# BreakBoard.net
KiCad netlist of a schematic drawn in Altium Designer
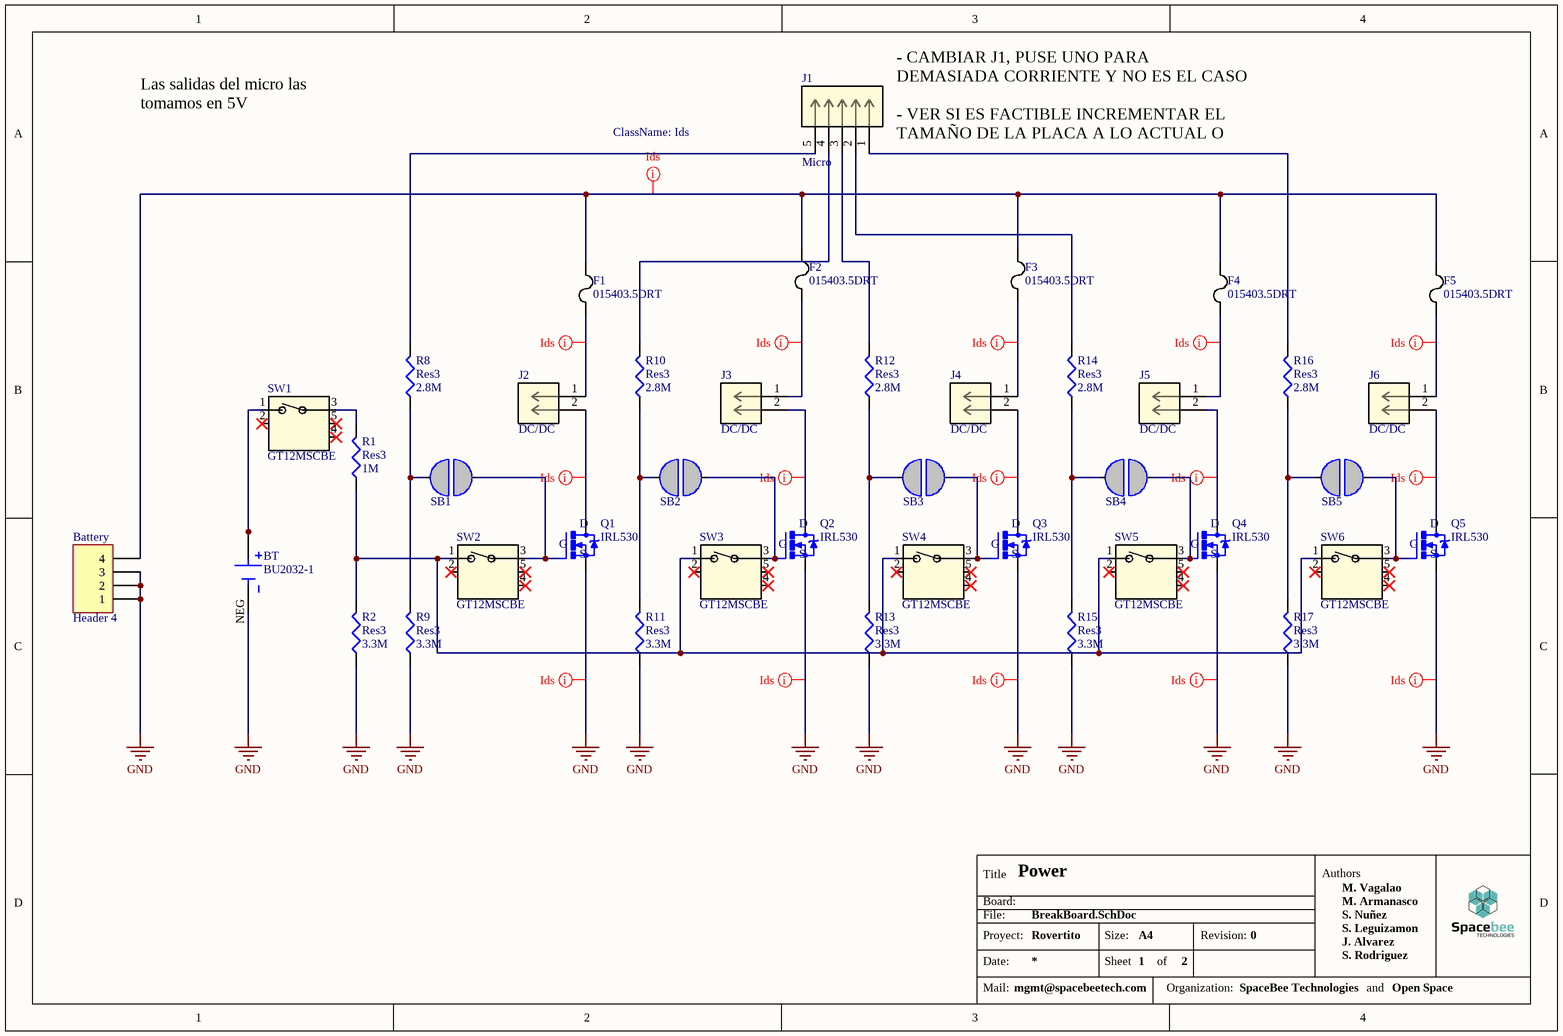
[diagram p0: BreakBoard.SchDoc]

(export (version "E")
  (design (tool "Eeschema 10.0.6"))
  (components
    (comp (ref "Battery")
      (value "Header 4")
      (footprint "292132-4:292132-4_TYC")
      (description "Header, 4-Pin")
      (fields (field (name "PUBLISHER") "Altium Limited"))
      (libsource (lib "Miscellaneous Connectors") (part "Header 4"))
    )
    (comp (ref "BT")
      (value "BU2032-1")
      (footprint "BAT_BU2032-1:BAT_BU2032-1")
      (description "HOLDER CR2032 W/ PC PINS")
      (fields (field (name "MF") "MPD"))
      (libsource (lib "BU2032-1") (part "BU2032-1"))
    )
    (comp (ref "F1")
      (value "015403.5DRT")
      (footprint "FUSE_Bourns")
      (description "No Description Available")
      (fields (field (name "COPYRIGHT") "Copyright (C) 2022 Ultra Librarian. All rights reserved."))
      (libsource (lib "015403P5DRT") (part "015403.5DRT"))
    )
    (comp (ref "F2")
      (value "015403.5DRT")
      (footprint "FUSE_Bourns")
      (description "No Description Available")
      (fields (field (name "COPYRIGHT") "Copyright (C) 2022 Ultra Librarian. All rights reserved."))
      (libsource (lib "015403P5DRT") (part "015403.5DRT"))
    )
    (comp (ref "F3")
      (value "015403.5DRT")
      (footprint "FUSE_Bourns")
      (description "No Description Available")
      (fields (field (name "COPYRIGHT") "Copyright (C) 2022 Ultra Librarian. All rights reserved."))
      (libsource (lib "015403P5DRT") (part "015403.5DRT"))
    )
    (comp (ref "F4")
      (value "015403.5DRT")
      (footprint "FUSE_Bourns")
      (description "No Description Available")
      (fields (field (name "COPYRIGHT") "Copyright (C) 2022 Ultra Librarian. All rights reserved."))
      (libsource (lib "015403P5DRT") (part "015403.5DRT"))
    )
    (comp (ref "F5")
      (value "015403.5DRT")
      (footprint "FUSE_Bourns")
      (description "No Description Available")
      (fields (field (name "COPYRIGHT") "Copyright (C) 2022 Ultra Librarian. All rights reserved."))
      (libsource (lib "015403P5DRT") (part "015403.5DRT"))
    )
    (comp (ref "J1")
      (value "Micro")
      (footprint "MOLEX_532610571")
      (description "No Description Available")
      (fields
        (field (name "MANUFACTURER_PART_NUMBER") "HTSW-105-07-L-S")
        (field (name "COPYRIGHT") "Copyright (C) 2022 Ultra Librarian. All rights reserved.")
      )
      (libsource (lib "HTSW-105-07-L-S") (part "HTSW-105-07-L-S"))
    )
    (comp (ref "J2")
      (value "DC/DC")
      (footprint "CON_1054302102_MOL")
      (description "No Description Available")
      (fields
        (field (name "MANUFACTURER_PART_NUMBER") "TSW-102-05-T-S")
        (field (name "COPYRIGHT") "Copyright (C) 2022 Ultra Librarian. All rights reserved.")
      )
      (libsource (lib "TSW-102-05-T-S") (part "TSW-102-05-T-S"))
    )
    (comp (ref "J3")
      (value "DC/DC")
      (footprint "CON_1054302102_MOL")
      (description "No Description Available")
      (fields
        (field (name "MANUFACTURER_PART_NUMBER") "TSW-102-05-T-S")
        (field (name "COPYRIGHT") "Copyright (C) 2022 Ultra Librarian. All rights reserved.")
      )
      (libsource (lib "TSW-102-05-T-S") (part "TSW-102-05-T-S"))
    )
    (comp (ref "J4")
      (value "DC/DC")
      (footprint "CON_1054302102_MOL")
      (description "No Description Available")
      (fields
        (field (name "MANUFACTURER_PART_NUMBER") "TSW-102-05-T-S")
        (field (name "COPYRIGHT") "Copyright (C) 2022 Ultra Librarian. All rights reserved.")
      )
      (libsource (lib "TSW-102-05-T-S") (part "TSW-102-05-T-S"))
    )
    (comp (ref "J5")
      (value "DC/DC")
      (footprint "CON_1054302102_MOL")
      (description "No Description Available")
      (fields
        (field (name "MANUFACTURER_PART_NUMBER") "TSW-102-05-T-S")
        (field (name "COPYRIGHT") "Copyright (C) 2022 Ultra Librarian. All rights reserved.")
      )
      (libsource (lib "TSW-102-05-T-S") (part "TSW-102-05-T-S"))
    )
    (comp (ref "J6")
      (value "DC/DC")
      (footprint "CON_1054302102_MOL")
      (description "No Description Available")
      (fields
        (field (name "MANUFACTURER_PART_NUMBER") "TSW-102-05-T-S")
        (field (name "COPYRIGHT") "Copyright (C) 2022 Ultra Librarian. All rights reserved.")
      )
      (libsource (lib "TSW-102-05-T-S") (part "TSW-102-05-T-S"))
    )
    (comp (ref "Q1")
      (value "IRL530")
      (footprint "IRL530NSTRLPBF:IRL530NSTRLPBF_INF")
      (description "N-Channel 100V 15A (Tc) 88W (Tc) Through Hole TO-220AB")
      (fields (field (name "MF") "Vishay / Siliconix"))
      (libsource (lib "IRL530") (part "IRL530"))
    )
    (comp (ref "Q2")
      (value "IRL530")
      (footprint "IRL530NSTRLPBF:IRL530NSTRLPBF_INF")
      (description "N-Channel 100V 15A (Tc) 88W (Tc) Through Hole TO-220AB")
      (fields (field (name "MF") "Vishay / Siliconix"))
      (libsource (lib "IRL530") (part "IRL530"))
    )
    (comp (ref "Q3")
      (value "IRL530")
      (footprint "IRL530NSTRLPBF:IRL530NSTRLPBF_INF")
      (description "N-Channel 100V 15A (Tc) 88W (Tc) Through Hole TO-220AB")
      (fields (field (name "MF") "Vishay / Siliconix"))
      (libsource (lib "IRL530") (part "IRL530"))
    )
    (comp (ref "Q4")
      (value "IRL530")
      (footprint "IRL530NSTRLPBF:IRL530NSTRLPBF_INF")
      (description "N-Channel 100V 15A (Tc) 88W (Tc) Through Hole TO-220AB")
      (fields (field (name "MF") "Vishay / Siliconix"))
      (libsource (lib "IRL530") (part "IRL530"))
    )
    (comp (ref "Q5")
      (value "IRL530")
      (footprint "IRL530NSTRLPBF:IRL530NSTRLPBF_INF")
      (description "N-Channel 100V 15A (Tc) 88W (Tc) Through Hole TO-220AB")
      (fields (field (name "MF") "Vishay / Siliconix"))
      (libsource (lib "IRL530") (part "IRL530"))
    )
    (comp (ref "R1")
      (value "Res3")
      (footprint "J1-0603")
      (description "Resistor")
      (fields (field (name "ALTIUM_VALUE") "1M") (field (name "PUBLISHER") "Altium Limited"))
      (libsource (lib "Miscellaneous Devices") (part "Res3"))
    )
    (comp (ref "R2")
      (value "Res3")
      (footprint "J1-0603")
      (description "Resistor")
      (fields (field (name "ALTIUM_VALUE") "3.3M") (field (name "PUBLISHER") "Altium Limited"))
      (libsource (lib "Miscellaneous Devices") (part "Res3"))
    )
    (comp (ref "R8")
      (value "Res3")
      (footprint "RESC2012X60N:RESC2012X60N")
      (description "Resistor")
      (fields (field (name "ALTIUM_VALUE") "2.8M") (field (name "PUBLISHER") "Altium Limited"))
      (libsource (lib "Miscellaneous Devices") (part "Res3"))
    )
    (comp (ref "R9")
      (value "Res3")
      (footprint "J1-0603")
      (description "Resistor")
      (fields (field (name "ALTIUM_VALUE") "3.3M") (field (name "PUBLISHER") "Altium Limited"))
      (libsource (lib "Miscellaneous Devices") (part "Res3"))
    )
    (comp (ref "R10")
      (value "Res3")
      (footprint "RESC2012X60N:RESC2012X60N")
      (description "Resistor")
      (fields (field (name "ALTIUM_VALUE") "2.8M") (field (name "PUBLISHER") "Altium Limited"))
      (libsource (lib "Miscellaneous Devices") (part "Res3"))
    )
    (comp (ref "R11")
      (value "Res3")
      (footprint "J1-0603")
      (description "Resistor")
      (fields (field (name "ALTIUM_VALUE") "3.3M") (field (name "PUBLISHER") "Altium Limited"))
      (libsource (lib "Miscellaneous Devices") (part "Res3"))
    )
    (comp (ref "R12")
      (value "Res3")
      (footprint "RESC2012X60N:RESC2012X60N")
      (description "Resistor")
      (fields (field (name "ALTIUM_VALUE") "2.8M") (field (name "PUBLISHER") "Altium Limited"))
      (libsource (lib "Miscellaneous Devices") (part "Res3"))
    )
    (comp (ref "R13")
      (value "Res3")
      (footprint "J1-0603")
      (description "Resistor")
      (fields (field (name "ALTIUM_VALUE") "3.3M") (field (name "PUBLISHER") "Altium Limited"))
      (libsource (lib "Miscellaneous Devices") (part "Res3"))
    )
    (comp (ref "R14")
      (value "Res3")
      (footprint "RESC2012X60N:RESC2012X60N")
      (description "Resistor")
      (fields (field (name "ALTIUM_VALUE") "2.8M") (field (name "PUBLISHER") "Altium Limited"))
      (libsource (lib "Miscellaneous Devices") (part "Res3"))
    )
    (comp (ref "R15")
      (value "Res3")
      (footprint "J1-0603")
      (description "Resistor")
      (fields (field (name "ALTIUM_VALUE") "3.3M") (field (name "PUBLISHER") "Altium Limited"))
      (libsource (lib "Miscellaneous Devices") (part "Res3"))
    )
    (comp (ref "R16")
      (value "Res3")
      (footprint "RESC2012X60N:RESC2012X60N")
      (description "Resistor")
      (fields (field (name "ALTIUM_VALUE") "2.8M") (field (name "PUBLISHER") "Altium Limited"))
      (libsource (lib "Miscellaneous Devices") (part "Res3"))
    )
    (comp (ref "R17")
      (value "Res3")
      (footprint "J1-0603")
      (description "Resistor")
      (fields (field (name "ALTIUM_VALUE") "3.3M") (field (name "PUBLISHER") "Altium Limited"))
      (libsource (lib "Miscellaneous Devices") (part "Res3"))
    )
    (comp (ref "SB1")
      (value "SolderBridge")
      (footprint "PCBComponent_1")
      (libsource (lib "SolderBridge") (part "Component_1"))
    )
    (comp (ref "SB2")
      (value "SolderBridge")
      (footprint "PCBComponent_1")
      (libsource (lib "SolderBridge") (part "Component_1"))
    )
    (comp (ref "SB3")
      (value "SolderBridge")
      (footprint "PCBComponent_1")
      (libsource (lib "SolderBridge") (part "Component_1"))
    )
    (comp (ref "SB4")
      (value "SolderBridge")
      (footprint "PCBComponent_1")
      (libsource (lib "SolderBridge") (part "Component_1"))
    )
    (comp (ref "SB5")
      (value "SolderBridge")
      (footprint "PCBComponent_1")
      (libsource (lib "SolderBridge") (part "Component_1"))
    )
    (comp (ref "SW1")
      (value "GT12MSCBE")
      (footprint "SW5_GT12MSCBE_CNK")
      (description "No Description Available")
      (fields (field (name "COPYRIGHT") "Copyright (C) 2022 Ultra Librarian. All rights reserved."))
      (libsource (lib "GT12MSCBE") (part "GT12MSCBE"))
    )
    (comp (ref "SW2")
      (value "GT12MSCBE")
      (footprint "SW5_GT12MSCBE_CNK")
      (description "No Description Available")
      (fields (field (name "COPYRIGHT") "Copyright (C) 2022 Ultra Librarian. All rights reserved."))
      (libsource (lib "GT12MSCBE") (part "GT12MSCBE"))
    )
    (comp (ref "SW3")
      (value "GT12MSCBE")
      (footprint "SW5_GT12MSCBE_CNK")
      (description "No Description Available")
      (fields (field (name "COPYRIGHT") "Copyright (C) 2022 Ultra Librarian. All rights reserved."))
      (libsource (lib "GT12MSCBE") (part "GT12MSCBE"))
    )
    (comp (ref "SW4")
      (value "GT12MSCBE")
      (footprint "SW5_GT12MSCBE_CNK")
      (description "No Description Available")
      (fields (field (name "COPYRIGHT") "Copyright (C) 2022 Ultra Librarian. All rights reserved."))
      (libsource (lib "GT12MSCBE") (part "GT12MSCBE"))
    )
    (comp (ref "SW5")
      (value "GT12MSCBE")
      (footprint "SW5_GT12MSCBE_CNK")
      (description "No Description Available")
      (fields (field (name "COPYRIGHT") "Copyright (C) 2022 Ultra Librarian. All rights reserved."))
      (libsource (lib "GT12MSCBE") (part "GT12MSCBE"))
    )
    (comp (ref "SW6")
      (value "GT12MSCBE")
      (footprint "SW5_GT12MSCBE_CNK")
      (description "No Description Available")
      (fields (field (name "COPYRIGHT") "Copyright (C) 2022 Ultra Librarian. All rights reserved."))
      (libsource (lib "GT12MSCBE") (part "GT12MSCBE"))
    )
  )
  (nets
    (net (code "1") (name "GND") (class "Default")
      (node (ref "BT") (pin "NEG") (pinfunction "NEG_NEG") (pintype "passive"))
      (node (ref "Battery") (pin "1") (pinfunction "1_1") (pintype "passive"))
      (node (ref "Battery") (pin "2") (pinfunction "2_2") (pintype "passive"))
      (node (ref "Battery") (pin "3") (pinfunction "3_3") (pintype "passive"))
      (node (ref "Q1") (pin "3") (pinfunction "S_3") (pintype "passive"))
      (node (ref "Q2") (pin "3") (pinfunction "S_3") (pintype "passive"))
      (node (ref "Q3") (pin "3") (pinfunction "S_3") (pintype "passive"))
      (node (ref "Q4") (pin "3") (pinfunction "S_3") (pintype "passive"))
      (node (ref "Q5") (pin "3") (pinfunction "S_3") (pintype "passive"))
      (node (ref "R11") (pin "1") (pinfunction "1_1") (pintype "passive"))
      (node (ref "R13") (pin "1") (pinfunction "1_1") (pintype "passive"))
      (node (ref "R15") (pin "1") (pinfunction "1_1") (pintype "passive"))
      (node (ref "R17") (pin "1") (pinfunction "1_1") (pintype "passive"))
      (node (ref "R2") (pin "1") (pinfunction "1_1") (pintype "passive"))
      (node (ref "R9") (pin "1") (pinfunction "1_1") (pintype "passive"))
    )
    (net (code "2") (name "Net-(BT-POS-PadS1+)") (class "Default")
      (node (ref "BT") (pin "S1+") (pinfunction "POS_S1+") (pintype "passive"))
      (node (ref "BT") (pin "S2+") (pinfunction "POS_S2+") (pintype "passive"))
      (node (ref "SW1") (pin "1") (pinfunction "1_1") (pintype "passive"))
    )
    (net (code "3") (name "Net-(Battery-Pad4)") (class "Default")
      (node (ref "Battery") (pin "4") (pinfunction "4_4") (pintype "passive"))
      (node (ref "F1") (pin "2") (pinfunction "2_2") (pintype "passive"))
      (node (ref "F2") (pin "2") (pinfunction "2_2") (pintype "passive"))
      (node (ref "F3") (pin "2") (pinfunction "2_2") (pintype "passive"))
      (node (ref "F4") (pin "2") (pinfunction "2_2") (pintype "passive"))
      (node (ref "F5") (pin "2") (pinfunction "2_2") (pintype "passive"))
    )
    (net (code "4") (name "Net-(F1-Pad1)") (class "Default")
      (node (ref "F1") (pin "1") (pinfunction "1_1") (pintype "passive"))
      (node (ref "J2") (pin "1") (pinfunction "1_1") (pintype "passive"))
    )
    (net (code "5") (name "Net-(F2-Pad1)") (class "Default")
      (node (ref "F2") (pin "1") (pinfunction "1_1") (pintype "passive"))
      (node (ref "J3") (pin "1") (pinfunction "1_1") (pintype "passive"))
    )
    (net (code "6") (name "Net-(F3-Pad1)") (class "Default")
      (node (ref "F3") (pin "1") (pinfunction "1_1") (pintype "passive"))
      (node (ref "J4") (pin "1") (pinfunction "1_1") (pintype "passive"))
    )
    (net (code "7") (name "Net-(F4-Pad1)") (class "Default")
      (node (ref "F4") (pin "1") (pinfunction "1_1") (pintype "passive"))
      (node (ref "J5") (pin "1") (pinfunction "1_1") (pintype "passive"))
    )
    (net (code "8") (name "Net-(F5-Pad1)") (class "Default")
      (node (ref "F5") (pin "1") (pinfunction "1_1") (pintype "passive"))
      (node (ref "J6") (pin "1") (pinfunction "1_1") (pintype "passive"))
    )
    (net (code "9") (name "Net-(J1-Pad1)") (class "Default")
      (node (ref "J1") (pin "1") (pinfunction "1_1") (pintype "passive"))
      (node (ref "R16") (pin "2") (pinfunction "2_2") (pintype "passive"))
    )
    (net (code "10") (name "Net-(J1-Pad2)") (class "Default")
      (node (ref "J1") (pin "2") (pinfunction "2_2") (pintype "passive"))
      (node (ref "R14") (pin "2") (pinfunction "2_2") (pintype "passive"))
    )
    (net (code "11") (name "Net-(J1-Pad3)") (class "Default")
      (node (ref "J1") (pin "3") (pinfunction "3_3") (pintype "passive"))
      (node (ref "R12") (pin "2") (pinfunction "2_2") (pintype "passive"))
    )
    (net (code "12") (name "Net-(J1-Pad4)") (class "Default")
      (node (ref "J1") (pin "4") (pinfunction "4_4") (pintype "passive"))
      (node (ref "R10") (pin "2") (pinfunction "2_2") (pintype "passive"))
    )
    (net (code "13") (name "Net-(J1-Pad5)") (class "Default")
      (node (ref "J1") (pin "5") (pinfunction "5_5") (pintype "passive"))
      (node (ref "R8") (pin "2") (pinfunction "2_2") (pintype "passive"))
    )
    (net (code "14") (name "Net-(Q1-D)") (class "Default")
      (node (ref "J2") (pin "2") (pinfunction "2_2") (pintype "passive"))
      (node (ref "Q1") (pin "2") (pinfunction "D_2") (pintype "passive"))
    )
    (net (code "15") (name "Net-(Q1-G)") (class "Default")
      (node (ref "Q1") (pin "1") (pinfunction "G_1") (pintype "passive"))
      (node (ref "SB1") (pin "0") (pinfunction "0_0") (pintype "passive"))
      (node (ref "SW2") (pin "3") (pinfunction "3_3") (pintype "passive"))
    )
    (net (code "16") (name "Net-(Q2-D)") (class "Default")
      (node (ref "J3") (pin "2") (pinfunction "2_2") (pintype "passive"))
      (node (ref "Q2") (pin "2") (pinfunction "D_2") (pintype "passive"))
    )
    (net (code "17") (name "Net-(Q2-G)") (class "Default")
      (node (ref "Q2") (pin "1") (pinfunction "G_1") (pintype "passive"))
      (node (ref "SB2") (pin "0") (pinfunction "0_0") (pintype "passive"))
      (node (ref "SW3") (pin "3") (pinfunction "3_3") (pintype "passive"))
    )
    (net (code "18") (name "Net-(Q3-D)") (class "Default")
      (node (ref "J4") (pin "2") (pinfunction "2_2") (pintype "passive"))
      (node (ref "Q3") (pin "2") (pinfunction "D_2") (pintype "passive"))
    )
    (net (code "19") (name "Net-(Q3-G)") (class "Default")
      (node (ref "Q3") (pin "1") (pinfunction "G_1") (pintype "passive"))
      (node (ref "SB3") (pin "0") (pinfunction "0_0") (pintype "passive"))
      (node (ref "SW4") (pin "3") (pinfunction "3_3") (pintype "passive"))
    )
    (net (code "20") (name "Net-(Q4-D)") (class "Default")
      (node (ref "J5") (pin "2") (pinfunction "2_2") (pintype "passive"))
      (node (ref "Q4") (pin "2") (pinfunction "D_2") (pintype "passive"))
    )
    (net (code "21") (name "Net-(Q4-G)") (class "Default")
      (node (ref "Q4") (pin "1") (pinfunction "G_1") (pintype "passive"))
      (node (ref "SB4") (pin "0") (pinfunction "0_0") (pintype "passive"))
      (node (ref "SW5") (pin "3") (pinfunction "3_3") (pintype "passive"))
    )
    (net (code "22") (name "Net-(Q5-D)") (class "Default")
      (node (ref "J6") (pin "2") (pinfunction "2_2") (pintype "passive"))
      (node (ref "Q5") (pin "2") (pinfunction "D_2") (pintype "passive"))
    )
    (net (code "23") (name "Net-(Q5-G)") (class "Default")
      (node (ref "Q5") (pin "1") (pinfunction "G_1") (pintype "passive"))
      (node (ref "SB5") (pin "0") (pinfunction "0_0") (pintype "passive"))
      (node (ref "SW6") (pin "3") (pinfunction "3_3") (pintype "passive"))
    )
    (net (code "24") (name "Net-(R1-Pad1)") (class "Default")
      (node (ref "R1") (pin "1") (pinfunction "1_1") (pintype "passive"))
      (node (ref "R2") (pin "2") (pinfunction "2_2") (pintype "passive"))
      (node (ref "SW2") (pin "1") (pinfunction "1_1") (pintype "passive"))
      (node (ref "SW3") (pin "1") (pinfunction "1_1") (pintype "passive"))
      (node (ref "SW4") (pin "1") (pinfunction "1_1") (pintype "passive"))
      (node (ref "SW5") (pin "1") (pinfunction "1_1") (pintype "passive"))
      (node (ref "SW6") (pin "1") (pinfunction "1_1") (pintype "passive"))
    )
    (net (code "25") (name "Net-(R1-Pad2)") (class "Default")
      (node (ref "R1") (pin "2") (pinfunction "2_2") (pintype "passive"))
      (node (ref "SW1") (pin "3") (pinfunction "3_3") (pintype "passive"))
    )
    (net (code "26") (name "Net-(R8-Pad1)") (class "Default")
      (node (ref "R8") (pin "1") (pinfunction "1_1") (pintype "passive"))
      (node (ref "R9") (pin "2") (pinfunction "2_2") (pintype "passive"))
      (node (ref "SB1") (pin "1") (pinfunction "1_1") (pintype "passive"))
    )
    (net (code "27") (name "Net-(R10-Pad1)") (class "Default")
      (node (ref "R10") (pin "1") (pinfunction "1_1") (pintype "passive"))
      (node (ref "R11") (pin "2") (pinfunction "2_2") (pintype "passive"))
      (node (ref "SB2") (pin "1") (pinfunction "1_1") (pintype "passive"))
    )
    (net (code "28") (name "Net-(R12-Pad1)") (class "Default")
      (node (ref "R12") (pin "1") (pinfunction "1_1") (pintype "passive"))
      (node (ref "R13") (pin "2") (pinfunction "2_2") (pintype "passive"))
      (node (ref "SB3") (pin "1") (pinfunction "1_1") (pintype "passive"))
    )
    (net (code "29") (name "Net-(R14-Pad1)") (class "Default")
      (node (ref "R14") (pin "1") (pinfunction "1_1") (pintype "passive"))
      (node (ref "R15") (pin "2") (pinfunction "2_2") (pintype "passive"))
      (node (ref "SB4") (pin "1") (pinfunction "1_1") (pintype "passive"))
    )
    (net (code "30") (name "Net-(R16-Pad1)") (class "Default")
      (node (ref "R16") (pin "1") (pinfunction "1_1") (pintype "passive"))
      (node (ref "R17") (pin "2") (pinfunction "2_2") (pintype "passive"))
      (node (ref "SB5") (pin "1") (pinfunction "1_1") (pintype "passive"))
    )
    (net (code "31") (name "unconnected-(SW1-6-Pad5)") (class "Default")
      (node (ref "SW1") (pin "5") (pinfunction "6_5") (pintype "passive+no_connect"))
    )
    (net (code "32") (name "unconnected-(SW1-Pad2)") (class "Default")
      (node (ref "SW1") (pin "2") (pinfunction "2_2") (pintype "passive+no_connect"))
    )
    (net (code "33") (name "unconnected-(SW1-Pad4)") (class "Default")
      (node (ref "SW1") (pin "4") (pinfunction "4_4") (pintype "passive+no_connect"))
    )
    (net (code "34") (name "unconnected-(SW2-6-Pad5)") (class "Default")
      (node (ref "SW2") (pin "5") (pinfunction "6_5") (pintype "passive+no_connect"))
    )
    (net (code "35") (name "unconnected-(SW2-Pad2)") (class "Default")
      (node (ref "SW2") (pin "2") (pinfunction "2_2") (pintype "passive+no_connect"))
    )
    (net (code "36") (name "unconnected-(SW2-Pad4)") (class "Default")
      (node (ref "SW2") (pin "4") (pinfunction "4_4") (pintype "passive+no_connect"))
    )
    (net (code "37") (name "unconnected-(SW3-6-Pad5)") (class "Default")
      (node (ref "SW3") (pin "5") (pinfunction "6_5") (pintype "passive+no_connect"))
    )
    (net (code "38") (name "unconnected-(SW3-Pad2)") (class "Default")
      (node (ref "SW3") (pin "2") (pinfunction "2_2") (pintype "passive+no_connect"))
    )
    (net (code "39") (name "unconnected-(SW3-Pad4)") (class "Default")
      (node (ref "SW3") (pin "4") (pinfunction "4_4") (pintype "passive+no_connect"))
    )
    (net (code "40") (name "unconnected-(SW4-6-Pad5)") (class "Default")
      (node (ref "SW4") (pin "5") (pinfunction "6_5") (pintype "passive+no_connect"))
    )
    (net (code "41") (name "unconnected-(SW4-Pad2)") (class "Default")
      (node (ref "SW4") (pin "2") (pinfunction "2_2") (pintype "passive+no_connect"))
    )
    (net (code "42") (name "unconnected-(SW4-Pad4)") (class "Default")
      (node (ref "SW4") (pin "4") (pinfunction "4_4") (pintype "passive+no_connect"))
    )
    (net (code "43") (name "unconnected-(SW5-6-Pad5)") (class "Default")
      (node (ref "SW5") (pin "5") (pinfunction "6_5") (pintype "passive+no_connect"))
    )
    (net (code "44") (name "unconnected-(SW5-Pad2)") (class "Default")
      (node (ref "SW5") (pin "2") (pinfunction "2_2") (pintype "passive+no_connect"))
    )
    (net (code "45") (name "unconnected-(SW5-Pad4)") (class "Default")
      (node (ref "SW5") (pin "4") (pinfunction "4_4") (pintype "passive+no_connect"))
    )
    (net (code "46") (name "unconnected-(SW6-6-Pad5)") (class "Default")
      (node (ref "SW6") (pin "5") (pinfunction "6_5") (pintype "passive+no_connect"))
    )
    (net (code "47") (name "unconnected-(SW6-Pad2)") (class "Default")
      (node (ref "SW6") (pin "2") (pinfunction "2_2") (pintype "passive+no_connect"))
    )
    (net (code "48") (name "unconnected-(SW6-Pad4)") (class "Default")
      (node (ref "SW6") (pin "4") (pinfunction "4_4") (pintype "passive+no_connect"))
    )
  )
)
